# trico_embed01_atmpt01.net
KiCad netlist of a schematic drawn in EAGLE
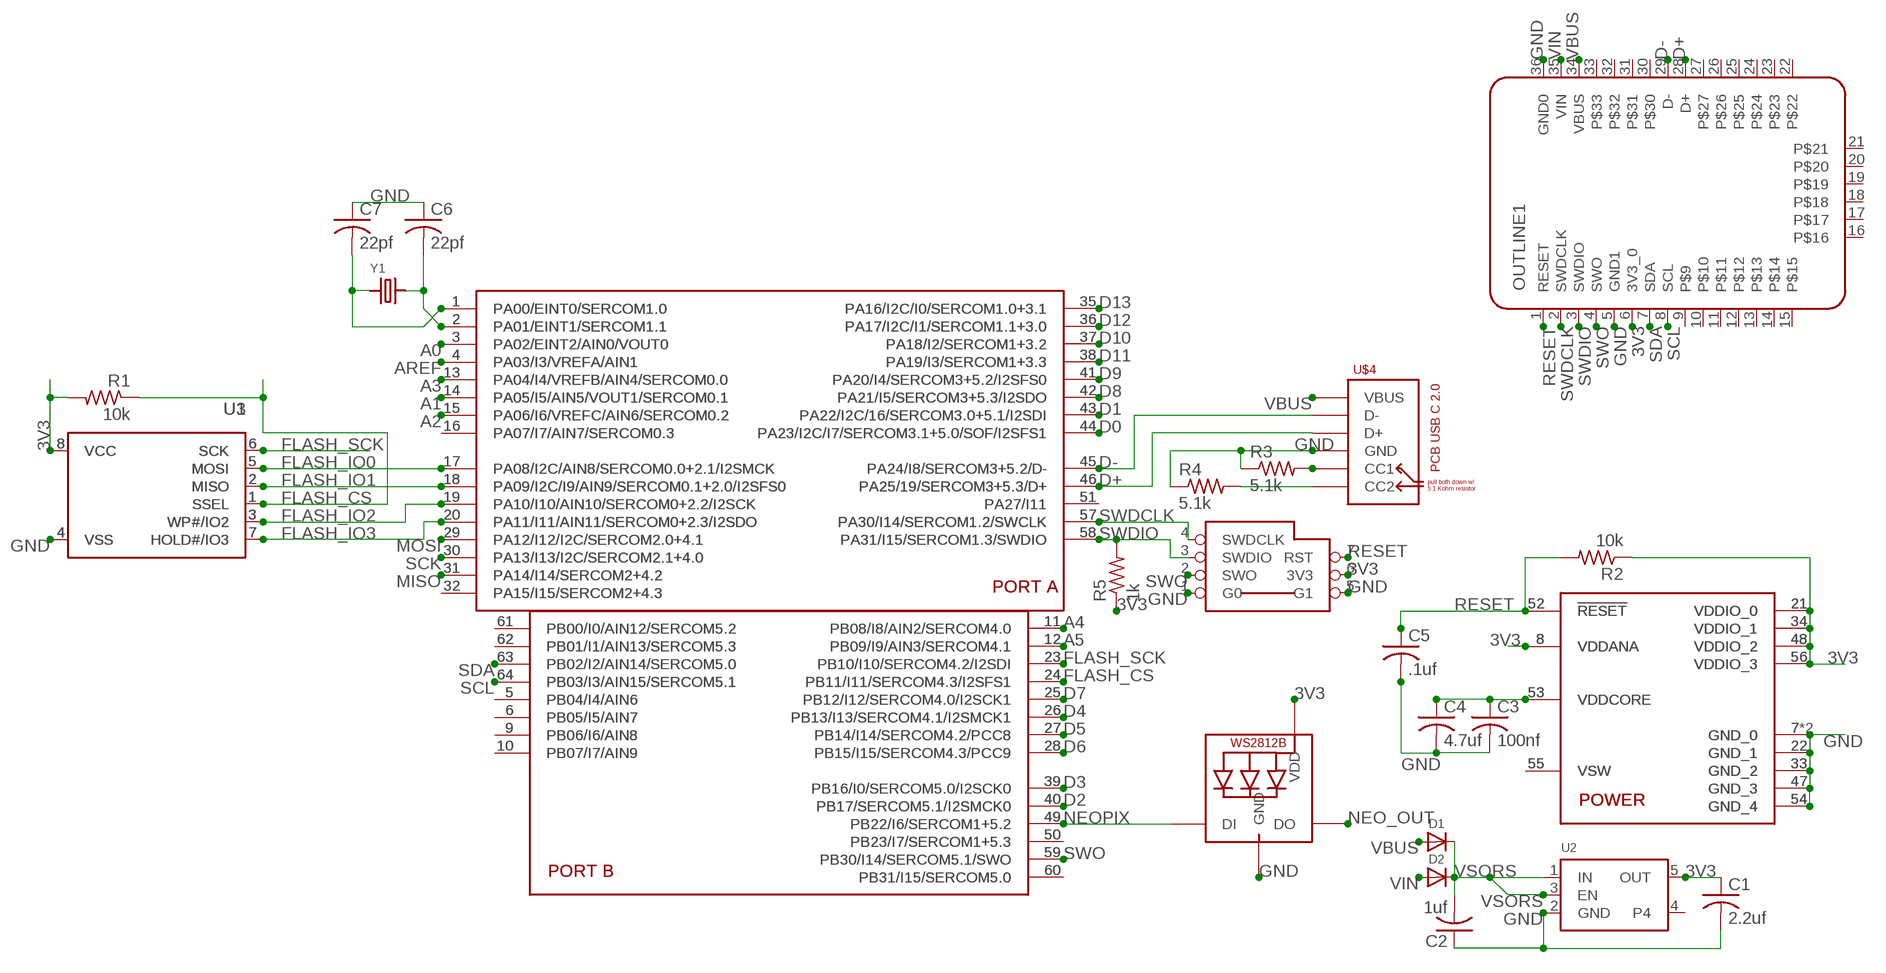
[diagram p0: schematic, sheet 1]

(export (version "E")
  (design (tool "Eeschema 10.0.6"))
  (components
    (comp (ref "C1")
      (value "2.2uf")
      (footprint "eagle-import:TG-C0805MP")
      (libsource (lib "eagle-import") (part "C-TG"))
    )
    (comp (ref "C2")
      (value "1uf")
      (footprint "eagle-import:TG-C0805MP")
      (libsource (lib "eagle-import") (part "C-TG"))
    )
    (comp (ref "C3")
      (value "100nf")
      (footprint "eagle-import:TG-C0805MP")
      (libsource (lib "eagle-import") (part "C-TG"))
    )
    (comp (ref "C4")
      (value "4.7uf")
      (footprint "eagle-import:TG-C0805MP")
      (libsource (lib "eagle-import") (part "C-TG"))
    )
    (comp (ref "C5")
      (value ".1uf")
      (footprint "eagle-import:TG-C0805MP")
      (libsource (lib "eagle-import") (part "C-TG"))
    )
    (comp (ref "C6")
      (value "22pf")
      (footprint "eagle-import:TG-C0805MP")
      (libsource (lib "eagle-import") (part "C-TG"))
    )
    (comp (ref "C7")
      (value "22pf")
      (footprint "eagle-import:TG-C0805MP")
      (libsource (lib "eagle-import") (part "C-TG"))
    )
    (comp (ref "D1")
      (value "DIODESOD-123")
      (footprint "eagle-import:SOD-123")
      (libsource (lib "eagle-import") (part "DIODESOD-123"))
    )
    (comp (ref "D2")
      (value "DIODESOD-123")
      (footprint "eagle-import:SOD-123")
      (libsource (lib "eagle-import") (part "DIODESOD-123"))
    )
    (comp (ref "LED1")
      (value "LED-NEO-WS2812B3535")
      (footprint "eagle-import:LED3535")
      (libsource (lib "eagle-import") (part "LED-NEO-WS2812B3535"))
    )
    (comp (ref "OUTLINE1")
      (value "TRIOC_DEV_36_EMBED_01BREAK")
      (footprint "eagle-import:TRICO_DEV_01_BRK_HYBRID")
      (libsource (lib "eagle-import") (part "TRIOC_DEV_36_EMBED_01BREAK"))
    )
    (comp (ref "R1")
      (value "10k")
      (footprint "eagle-import:TG-R0805")
      (libsource (lib "eagle-import") (part "R_TG"))
    )
    (comp (ref "R2")
      (value "10k")
      (footprint "eagle-import:TG-R0805")
      (libsource (lib "eagle-import") (part "R_TG"))
    )
    (comp (ref "R3")
      (value "5.1k")
      (footprint "eagle-import:TG-R0805")
      (libsource (lib "eagle-import") (part "0TG-Lib v01.4_R_TG"))
    )
    (comp (ref "R4")
      (value "5.1k")
      (footprint "eagle-import:TG-R0805")
      (libsource (lib "eagle-import") (part "0TG-Lib v01.4_R_TG"))
    )
    (comp (ref "R5")
      (value "1k")
      (footprint "eagle-import:TG-R0805")
      (libsource (lib "eagle-import") (part "R_TG"))
    )
    (comp (ref "U$1")
      (value "MCU-ATSAMD51J-ADATQFP")
      (footprint "eagle-import:QFP50P1200X1200X120-64N")
      (libsource (lib "eagle-import") (part "MCU-ATSAMD51J-ADATQFP"))
    )
    (comp (ref "U$2")
      (value "MCU-ATSAMD51J-ADAADA")
      (footprint "eagle-import:MICROBUILDER_PQFN64-1")
      (libsource (lib "eagle-import") (part "0TG-Lib v01.4_MCU-ATSAMD51J-ADAADA"))
    )
    (comp (ref "U$3")
      (value "SWD_POGO")
      (footprint "eagle-import:SWD_POGO")
      (libsource (lib "eagle-import") (part "SWD_POGO"))
    )
    (comp (ref "U$4")
      (value "USB-C-PCB-USB-2.0-TYPE-CDS_2")
      (footprint "eagle-import:USB_TYPE_C_DS_2")
      (libsource (lib "eagle-import") (part "USB-C-PCB-USB-2.0-TYPE-CDS_2"))
    )
    (comp (ref "U1")
      (value "FLASH-SPI-SOIC8")
      (footprint "eagle-import:SOIC8_150MIL")
      (libsource (lib "eagle-import") (part "FLASH-SPI-SOIC8"))
    )
    (comp (ref "U2")
      (value "VREG_STD_MIN_SOT23-5")
      (footprint "eagle-import:SOT23-5")
      (libsource (lib "eagle-import") (part "VREG_STD_MIN_SOT23-5"))
    )
    (comp (ref "U3")
      (value "FLASH-SPI-SOIC8208MIL")
      (footprint "eagle-import:SOIC8_208MIL")
      (libsource (lib "eagle-import") (part "FLASH-SPI-SOIC8208MIL"))
    )
    (comp (ref "Y1")
      (value "XTAL_ADA4.9X1.8")
      (footprint "eagle-import:MICROBUILDER_CRYSTAL_4.9X1.8")
      (libsource (lib "eagle-import") (part "XTAL_ADA4.9X1.8"))
    )
  )
  (nets
    (net (code "1") (name "/3V3") (class "Default")
      (node (ref "C1") (pin "1") (pinfunction "1_1") (pintype "passive"))
      (node (ref "LED1") (pin "2") (pinfunction "VDD_2") (pintype "power_in"))
      (node (ref "OUTLINE1") (pin "6") (pinfunction "3V3_0_6") (pintype "bidirectional"))
      (node (ref "R1") (pin "2") (pinfunction "2_2") (pintype "passive"))
      (node (ref "R2") (pin "1") (pinfunction "1_1") (pintype "passive"))
      (node (ref "R5") (pin "1") (pinfunction "1_1") (pintype "passive"))
      (node (ref "U$1") (pin "21") (pinfunction "VDDIO_0_21") (pintype "bidirectional"))
      (node (ref "U$1") (pin "34") (pinfunction "VDDIO_1_34") (pintype "bidirectional"))
      (node (ref "U$1") (pin "48") (pinfunction "VDDIO_2_48") (pintype "bidirectional"))
      (node (ref "U$1") (pin "56") (pinfunction "VDDIO_3_56") (pintype "bidirectional"))
      (node (ref "U$1") (pin "8") (pinfunction "VDDANA_8") (pintype "bidirectional"))
      (node (ref "U$2") (pin "21") (pinfunction "VDDIO_0_21") (pintype "bidirectional"))
      (node (ref "U$2") (pin "34") (pinfunction "VDDIO_1_34") (pintype "bidirectional"))
      (node (ref "U$2") (pin "48") (pinfunction "VDDIO_2_48") (pintype "bidirectional"))
      (node (ref "U$2") (pin "56") (pinfunction "VDDIO_3_56") (pintype "bidirectional"))
      (node (ref "U$2") (pin "8") (pinfunction "VDDANA_8") (pintype "bidirectional"))
      (node (ref "U$3") (pin "6") (pinfunction "3V3_6") (pintype "bidirectional"))
      (node (ref "U1") (pin "8") (pinfunction "VCC_8") (pintype "bidirectional"))
      (node (ref "U2") (pin "5") (pinfunction "OUT_5") (pintype "power_in"))
      (node (ref "U3") (pin "8") (pinfunction "VCC_8") (pintype "bidirectional"))
    )
    (net (code "2") (name "/A0") (class "Default")
      (node (ref "U$1") (pin "3") (pinfunction "PA02/EINT2/AIN0/VOUT0_3") (pintype "bidirectional"))
      (node (ref "U$2") (pin "3") (pinfunction "PA02/EINT2/AIN0/VOUT0_3") (pintype "bidirectional"))
    )
    (net (code "3") (name "/A1") (class "Default")
      (node (ref "U$1") (pin "14") (pinfunction "PA05/I5/AIN5/VOUT1/SERCOM0.1_14") (pintype "bidirectional"))
      (node (ref "U$2") (pin "14") (pinfunction "PA05/I5/AIN5/VOUT1/SERCOM0.1_14") (pintype "bidirectional"))
    )
    (net (code "4") (name "/A2") (class "Default")
      (node (ref "U$1") (pin "15") (pinfunction "PA06/I6/VREFC/AIN6/SERCOM0.2_15") (pintype "bidirectional"))
      (node (ref "U$2") (pin "15") (pinfunction "PA06/I6/VREFC/AIN6/SERCOM0.2_15") (pintype "bidirectional"))
    )
    (net (code "5") (name "/A3") (class "Default")
      (node (ref "U$1") (pin "13") (pinfunction "PA04/I4/VREFB/AIN4/SERCOM0.0_13") (pintype "bidirectional"))
      (node (ref "U$2") (pin "13") (pinfunction "PA04/I4/VREFB/AIN4/SERCOM0.0_13") (pintype "bidirectional"))
    )
    (net (code "6") (name "/A4") (class "Default")
      (node (ref "U$1") (pin "11") (pinfunction "PB08/I8/AIN2/SERCOM4.0_11") (pintype "bidirectional"))
      (node (ref "U$2") (pin "11") (pinfunction "PB08/I8/AIN2/SERCOM4.0_11") (pintype "bidirectional"))
    )
    (net (code "7") (name "/A5") (class "Default")
      (node (ref "U$1") (pin "12") (pinfunction "PB09/I9/AIN3/SERCOM4.1_12") (pintype "bidirectional"))
      (node (ref "U$2") (pin "12") (pinfunction "PB09/I9/AIN3/SERCOM4.1_12") (pintype "bidirectional"))
    )
    (net (code "8") (name "/AREF") (class "Default")
      (node (ref "U$1") (pin "4") (pinfunction "PA03/I3/VREFA/AIN1_4") (pintype "bidirectional"))
      (node (ref "U$2") (pin "4") (pinfunction "PA03/I3/VREFA/AIN1_4") (pintype "bidirectional"))
    )
    (net (code "9") (name "/D+") (class "Default")
      (node (ref "OUTLINE1") (pin "28") (pinfunction "D+_28") (pintype "bidirectional"))
      (node (ref "U$1") (pin "46") (pinfunction "PA25/19/SERCOM3+5.3/D+_46") (pintype "bidirectional"))
      (node (ref "U$2") (pin "46") (pinfunction "PA25/19/SERCOM3+5.3/D+_46") (pintype "bidirectional"))
      (node (ref "U$4") (pin "A6") (pinfunction "D+_A6") (pintype "bidirectional"))
      (node (ref "U$4") (pin "B6") (pinfunction "D+_B6") (pintype "bidirectional"))
    )
    (net (code "10") (name "/D-") (class "Default")
      (node (ref "OUTLINE1") (pin "29") (pinfunction "D-_29") (pintype "bidirectional"))
      (node (ref "U$1") (pin "45") (pinfunction "PA24/I8/SERCOM3+5.2/D-_45") (pintype "bidirectional"))
      (node (ref "U$2") (pin "45") (pinfunction "PA24/I8/SERCOM3+5.2/D-_45") (pintype "bidirectional"))
      (node (ref "U$4") (pin "A7") (pinfunction "D-_A7") (pintype "bidirectional"))
      (node (ref "U$4") (pin "B7") (pinfunction "D-_B7") (pintype "bidirectional"))
    )
    (net (code "11") (name "/D0") (class "Default")
      (node (ref "U$1") (pin "44") (pinfunction "PA23/I2C/I7/SERCOM3.1+5.0/SOF/I2SFS1_44") (pintype "bidirectional"))
      (node (ref "U$2") (pin "44") (pinfunction "PA23/I2C/I7/SERCOM3.1+5.0/SOF/I2SFS1_44") (pintype "bidirectional"))
    )
    (net (code "12") (name "/D1") (class "Default")
      (node (ref "U$1") (pin "43") (pinfunction "PA22/I2C/16/SERCOM3.0+5.1/I2SDI_43") (pintype "bidirectional"))
      (node (ref "U$2") (pin "43") (pinfunction "PA22/I2C/16/SERCOM3.0+5.1/I2SDI_43") (pintype "bidirectional"))
    )
    (net (code "13") (name "/D2") (class "Default")
      (node (ref "U$1") (pin "40") (pinfunction "PB17/SERCOM5.1/I2SMCK0_40") (pintype "bidirectional"))
      (node (ref "U$2") (pin "40") (pinfunction "PB17/SERCOM5.1/I2SMCK0_40") (pintype "bidirectional"))
    )
    (net (code "14") (name "/D3") (class "Default")
      (node (ref "U$1") (pin "39") (pinfunction "PB16/I0/SERCOM5.0/I2SCK0_39") (pintype "bidirectional"))
      (node (ref "U$2") (pin "39") (pinfunction "PB16/I0/SERCOM5.0/I2SCK0_39") (pintype "bidirectional"))
    )
    (net (code "15") (name "/D4") (class "Default")
      (node (ref "U$1") (pin "26") (pinfunction "PB13/I13/SERCOM4.1/I2SMCK1_26") (pintype "bidirectional"))
      (node (ref "U$2") (pin "26") (pinfunction "PB13/I13/SERCOM4.1/I2SMCK1_26") (pintype "bidirectional"))
    )
    (net (code "16") (name "/D5") (class "Default")
      (node (ref "U$1") (pin "27") (pinfunction "PB14/I14/SERCOM4.2/PCC8_27") (pintype "bidirectional"))
      (node (ref "U$2") (pin "27") (pinfunction "PB14/I14/SERCOM4.2/PCC8_27") (pintype "bidirectional"))
    )
    (net (code "17") (name "/D6") (class "Default")
      (node (ref "U$1") (pin "28") (pinfunction "PB15/I15/SERCOM4.3/PCC9_28") (pintype "bidirectional"))
      (node (ref "U$2") (pin "28") (pinfunction "PB15/I15/SERCOM4.3/PCC9_28") (pintype "bidirectional"))
    )
    (net (code "18") (name "/D7") (class "Default")
      (node (ref "U$1") (pin "25") (pinfunction "PB12/I12/SERCOM4.0/I2SCK1_25") (pintype "bidirectional"))
      (node (ref "U$2") (pin "25") (pinfunction "PB12/I12/SERCOM4.0/I2SCK1_25") (pintype "bidirectional"))
    )
    (net (code "19") (name "/D8") (class "Default")
      (node (ref "U$1") (pin "42") (pinfunction "PA21/I5/SERCOM3+5.3/I2SDO_42") (pintype "bidirectional"))
      (node (ref "U$2") (pin "42") (pinfunction "PA21/I5/SERCOM3+5.3/I2SDO_42") (pintype "bidirectional"))
    )
    (net (code "20") (name "/D9") (class "Default")
      (node (ref "U$1") (pin "41") (pinfunction "PA20/I4/SERCOM3+5.2/I2SFS0_41") (pintype "bidirectional"))
      (node (ref "U$2") (pin "41") (pinfunction "PA20/I4/SERCOM3+5.2/I2SFS0_41") (pintype "bidirectional"))
    )
    (net (code "21") (name "/D10") (class "Default")
      (node (ref "U$1") (pin "37") (pinfunction "PA18/I2/SERCOM1+3.2_37") (pintype "bidirectional"))
      (node (ref "U$2") (pin "37") (pinfunction "PA18/I2/SERCOM1+3.2_37") (pintype "bidirectional"))
    )
    (net (code "22") (name "/D11") (class "Default")
      (node (ref "U$1") (pin "38") (pinfunction "PA19/I3/SERCOM1+3.3_38") (pintype "bidirectional"))
      (node (ref "U$2") (pin "38") (pinfunction "PA19/I3/SERCOM1+3.3_38") (pintype "bidirectional"))
    )
    (net (code "23") (name "/D12") (class "Default")
      (node (ref "U$1") (pin "36") (pinfunction "PA17/I2C/I1/SERCOM1.1+3.0_36") (pintype "bidirectional"))
      (node (ref "U$2") (pin "36") (pinfunction "PA17/I2C/I1/SERCOM1.1+3.0_36") (pintype "bidirectional"))
    )
    (net (code "24") (name "/D13") (class "Default")
      (node (ref "U$1") (pin "35") (pinfunction "PA16/I2C/I0/SERCOM1.0+3.1_35") (pintype "bidirectional"))
      (node (ref "U$2") (pin "35") (pinfunction "PA16/I2C/I0/SERCOM1.0+3.1_35") (pintype "bidirectional"))
    )
    (net (code "25") (name "/FLASH_CS") (class "Default")
      (node (ref "R1") (pin "1") (pinfunction "1_1") (pintype "passive"))
      (node (ref "U$1") (pin "24") (pinfunction "PB11/I11/SERCOM4.3/I2SFS1_24") (pintype "bidirectional"))
      (node (ref "U$2") (pin "24") (pinfunction "PB11/I11/SERCOM4.3/I2SFS1_24") (pintype "bidirectional"))
      (node (ref "U1") (pin "1") (pinfunction "SSEL_1") (pintype "bidirectional"))
      (node (ref "U3") (pin "1") (pinfunction "SSEL_1") (pintype "bidirectional"))
    )
    (net (code "26") (name "/FLASH_IO0") (class "Default")
      (node (ref "U$1") (pin "17") (pinfunction "PA08/I2C/AIN8/SERCOM0.0+2.1/I2SMCK_17") (pintype "bidirectional"))
      (node (ref "U$2") (pin "17") (pinfunction "PA08/I2C/AIN8/SERCOM0.0+2.1/I2SMCK_17") (pintype "bidirectional"))
      (node (ref "U1") (pin "5") (pinfunction "MOSI_5") (pintype "bidirectional"))
      (node (ref "U3") (pin "5") (pinfunction "MOSI_5") (pintype "bidirectional"))
    )
    (net (code "27") (name "/FLASH_IO1") (class "Default")
      (node (ref "U$1") (pin "18") (pinfunction "PA09/I2C/I9/AIN9/SERCOM0.1+2.0/I2SFS0_18") (pintype "bidirectional"))
      (node (ref "U$2") (pin "18") (pinfunction "PA09/I2C/I9/AIN9/SERCOM0.1+2.0/I2SFS0_18") (pintype "bidirectional"))
      (node (ref "U1") (pin "2") (pinfunction "MISO_2") (pintype "bidirectional"))
      (node (ref "U3") (pin "2") (pinfunction "MISO_2") (pintype "bidirectional"))
    )
    (net (code "28") (name "/FLASH_IO2") (class "Default")
      (node (ref "U$1") (pin "19") (pinfunction "PA10/I10/AIN10/SERCOM0+2.2/I2SCK_19") (pintype "bidirectional"))
      (node (ref "U$2") (pin "19") (pinfunction "PA10/I10/AIN10/SERCOM0+2.2/I2SCK_19") (pintype "bidirectional"))
      (node (ref "U1") (pin "3") (pinfunction "WP#/IO2_3") (pintype "bidirectional"))
      (node (ref "U3") (pin "3") (pinfunction "WP#/IO2_3") (pintype "bidirectional"))
    )
    (net (code "29") (name "/FLASH_IO3") (class "Default")
      (node (ref "U$1") (pin "20") (pinfunction "PA11/I11/AIN11/SERCOM0+2.3/I2SDO_20") (pintype "bidirectional"))
      (node (ref "U$2") (pin "20") (pinfunction "PA11/I11/AIN11/SERCOM0+2.3/I2SDO_20") (pintype "bidirectional"))
      (node (ref "U1") (pin "7") (pinfunction "HOLD#/IO3_7") (pintype "bidirectional"))
      (node (ref "U3") (pin "7") (pinfunction "HOLD#/IO3_7") (pintype "bidirectional"))
    )
    (net (code "30") (name "/FLASH_SCK") (class "Default")
      (node (ref "U$1") (pin "23") (pinfunction "PB10/I10/SERCOM4.2/I2SDI_23") (pintype "bidirectional"))
      (node (ref "U$2") (pin "23") (pinfunction "PB10/I10/SERCOM4.2/I2SDI_23") (pintype "bidirectional"))
      (node (ref "U1") (pin "6") (pinfunction "SCK_6") (pintype "bidirectional"))
      (node (ref "U3") (pin "6") (pinfunction "SCK_6") (pintype "bidirectional"))
    )
    (net (code "31") (name "/GND") (class "Default")
      (node (ref "C1") (pin "2") (pinfunction "2_2") (pintype "passive"))
      (node (ref "C2") (pin "1") (pinfunction "1_1") (pintype "passive"))
      (node (ref "C3") (pin "2") (pinfunction "2_2") (pintype "passive"))
      (node (ref "C4") (pin "2") (pinfunction "2_2") (pintype "passive"))
      (node (ref "C5") (pin "2") (pinfunction "2_2") (pintype "passive"))
      (node (ref "C6") (pin "1") (pinfunction "1_1") (pintype "passive"))
      (node (ref "C7") (pin "1") (pinfunction "1_1") (pintype "passive"))
      (node (ref "LED1") (pin "4") (pinfunction "GND_4") (pintype "power_in"))
      (node (ref "OUTLINE1") (pin "36") (pinfunction "GND0_36") (pintype "bidirectional"))
      (node (ref "OUTLINE1") (pin "5") (pinfunction "GND1_5") (pintype "bidirectional"))
      (node (ref "R3") (pin "1") (pinfunction "1_1") (pintype "passive"))
      (node (ref "R4") (pin "1") (pinfunction "1_1") (pintype "passive"))
      (node (ref "U$1") (pin "22") (pinfunction "GND_1_22") (pintype "bidirectional"))
      (node (ref "U$1") (pin "33") (pinfunction "GND_2_33") (pintype "bidirectional"))
      (node (ref "U$1") (pin "47") (pinfunction "GND_3_47") (pintype "bidirectional"))
      (node (ref "U$1") (pin "54") (pinfunction "GND_4_54") (pintype "bidirectional"))
      (node (ref "U$1") (pin "7") (pinfunction "GND_0_7") (pintype "bidirectional"))
      (node (ref "U$2") (pin "22") (pinfunction "GND_1_22") (pintype "bidirectional"))
      (node (ref "U$2") (pin "33") (pinfunction "GND_2_33") (pintype "bidirectional"))
      (node (ref "U$2") (pin "47") (pinfunction "GND_3_47") (pintype "bidirectional"))
      (node (ref "U$2") (pin "54") (pinfunction "GND_4_54") (pintype "bidirectional"))
      (node (ref "U$2") (pin "7") (pinfunction "GND_0_7") (pintype "bidirectional"))
      (node (ref "U$2") (pin "EXP") (pinfunction "GND_0_EXP") (pintype "bidirectional"))
      (node (ref "U$3") (pin "1") (pinfunction "G0_1") (pintype "bidirectional"))
      (node (ref "U$3") (pin "5") (pinfunction "G1_5") (pintype "bidirectional"))
      (node (ref "U$4") (pin "A1") (pinfunction "GND_A1") (pintype "bidirectional"))
      (node (ref "U$4") (pin "A12") (pinfunction "GND_A12") (pintype "bidirectional"))
      (node (ref "U$4") (pin "B1") (pinfunction "GND_B1") (pintype "bidirectional"))
      (node (ref "U$4") (pin "B12") (pinfunction "GND_B12") (pintype "bidirectional"))
      (node (ref "U1") (pin "4") (pinfunction "VSS_4") (pintype "bidirectional"))
      (node (ref "U2") (pin "2") (pinfunction "GND_2") (pintype "power_in"))
      (node (ref "U3") (pin "4") (pinfunction "VSS_4") (pintype "bidirectional"))
    )
    (net (code "32") (name "/MISO") (class "Default")
      (node (ref "U$1") (pin "31") (pinfunction "PA14/I14/SERCOM2+4.2_31") (pintype "bidirectional"))
      (node (ref "U$2") (pin "31") (pinfunction "PA14/I14/SERCOM2+4.2_31") (pintype "bidirectional"))
    )
    (net (code "33") (name "/MOSI") (class "Default")
      (node (ref "U$1") (pin "29") (pinfunction "PA12/I12/I2C/SERCOM2.0+4.1_29") (pintype "bidirectional"))
      (node (ref "U$2") (pin "29") (pinfunction "PA12/I12/I2C/SERCOM2.0+4.1_29") (pintype "bidirectional"))
    )
    (net (code "34") (name "/NEOPIX") (class "Default")
      (node (ref "LED1") (pin "1") (pinfunction "DI_1") (pintype "input"))
      (node (ref "U$1") (pin "49") (pinfunction "PB22/I6/SERCOM1+5.2_49") (pintype "bidirectional"))
      (node (ref "U$2") (pin "49") (pinfunction "PB22/I6/SERCOM1+5.2_49") (pintype "bidirectional"))
    )
    (net (code "35") (name "/NEO_OUT") (class "Default")
      (node (ref "LED1") (pin "3") (pinfunction "DO_3") (pintype "output"))
    )
    (net (code "36") (name "/RESET") (class "Default")
      (node (ref "C5") (pin "1") (pinfunction "1_1") (pintype "passive"))
      (node (ref "OUTLINE1") (pin "1") (pinfunction "RESET_1") (pintype "bidirectional"))
      (node (ref "R2") (pin "2") (pinfunction "2_2") (pintype "passive"))
      (node (ref "U$1") (pin "52") (pinfunction "~{RESET}_52") (pintype "bidirectional"))
      (node (ref "U$2") (pin "52") (pinfunction "~{RESET}_52") (pintype "bidirectional"))
      (node (ref "U$3") (pin "7") (pinfunction "RST_7") (pintype "bidirectional"))
    )
    (net (code "37") (name "/SCK") (class "Default")
      (node (ref "U$1") (pin "30") (pinfunction "PA13/I13/I2C/SERCOM2.1+4.0_30") (pintype "bidirectional"))
      (node (ref "U$2") (pin "30") (pinfunction "PA13/I13/I2C/SERCOM2.1+4.0_30") (pintype "bidirectional"))
    )
    (net (code "38") (name "/SCL") (class "Default")
      (node (ref "OUTLINE1") (pin "8") (pinfunction "SCL_8") (pintype "bidirectional"))
      (node (ref "U$1") (pin "64") (pinfunction "PB03/I3/AIN15/SERCOM5.1_64") (pintype "bidirectional"))
      (node (ref "U$2") (pin "64") (pinfunction "PB03/I3/AIN15/SERCOM5.1_64") (pintype "bidirectional"))
    )
    (net (code "39") (name "/SDA") (class "Default")
      (node (ref "OUTLINE1") (pin "7") (pinfunction "SDA_7") (pintype "bidirectional"))
      (node (ref "U$1") (pin "63") (pinfunction "PB02/I2/AIN14/SERCOM5.0_63") (pintype "bidirectional"))
      (node (ref "U$2") (pin "63") (pinfunction "PB02/I2/AIN14/SERCOM5.0_63") (pintype "bidirectional"))
    )
    (net (code "40") (name "/SWDCLK") (class "Default")
      (node (ref "OUTLINE1") (pin "2") (pinfunction "SWDCLK_2") (pintype "bidirectional"))
      (node (ref "U$1") (pin "57") (pinfunction "PA30/I14/SERCOM1.2/SWCLK_57") (pintype "bidirectional"))
      (node (ref "U$2") (pin "57") (pinfunction "PA30/I14/SERCOM1.2/SWCLK_57") (pintype "bidirectional"))
      (node (ref "U$3") (pin "4") (pinfunction "SWDCLK_4") (pintype "bidirectional"))
    )
    (net (code "41") (name "/SWDIO") (class "Default")
      (node (ref "OUTLINE1") (pin "3") (pinfunction "SWDIO_3") (pintype "bidirectional"))
      (node (ref "R5") (pin "2") (pinfunction "2_2") (pintype "passive"))
      (node (ref "U$1") (pin "58") (pinfunction "PA31/I15/SERCOM1.3/SWDIO_58") (pintype "bidirectional"))
      (node (ref "U$2") (pin "58") (pinfunction "PA31/I15/SERCOM1.3/SWDIO_58") (pintype "bidirectional"))
      (node (ref "U$3") (pin "3") (pinfunction "SWDIO_3") (pintype "bidirectional"))
    )
    (net (code "42") (name "/SWO") (class "Default")
      (node (ref "OUTLINE1") (pin "4") (pinfunction "SWO_4") (pintype "bidirectional"))
      (node (ref "U$1") (pin "59") (pinfunction "PB30/I14/SERCOM5.1/SWO_59") (pintype "bidirectional"))
      (node (ref "U$2") (pin "59") (pinfunction "PB30/I14/SERCOM5.1/SWO_59") (pintype "bidirectional"))
      (node (ref "U$3") (pin "2") (pinfunction "SWO_2") (pintype "bidirectional"))
    )
    (net (code "43") (name "/VBUS") (class "Default")
      (node (ref "D1") (pin "A") (pinfunction "A_A") (pintype "passive"))
      (node (ref "OUTLINE1") (pin "34") (pinfunction "VBUS_34") (pintype "bidirectional"))
      (node (ref "U$4") (pin "A4") (pinfunction "VBUS_A4") (pintype "bidirectional"))
      (node (ref "U$4") (pin "A9") (pinfunction "VBUS_A9") (pintype "bidirectional"))
      (node (ref "U$4") (pin "B4") (pinfunction "VBUS_B4") (pintype "bidirectional"))
      (node (ref "U$4") (pin "B9") (pinfunction "VBUS_B9") (pintype "bidirectional"))
    )
    (net (code "44") (name "/VIN") (class "Default")
      (node (ref "D2") (pin "A") (pinfunction "A_A") (pintype "passive"))
      (node (ref "OUTLINE1") (pin "35") (pinfunction "VIN_35") (pintype "bidirectional"))
    )
    (net (code "45") (name "/VSORS") (class "Default")
      (node (ref "C2") (pin "2") (pinfunction "2_2") (pintype "passive"))
      (node (ref "D1") (pin "C") (pinfunction "C_C") (pintype "passive"))
      (node (ref "D2") (pin "C") (pinfunction "C_C") (pintype "passive"))
      (node (ref "U2") (pin "1") (pinfunction "IN_1") (pintype "power_in"))
      (node (ref "U2") (pin "3") (pinfunction "EN_3") (pintype "input"))
    )
    (net (code "46") (name "Net-(U$1A-PA00{slash}EINT0{slash}SERCOM1.0)") (class "Default")
      (node (ref "C7") (pin "2") (pinfunction "2_2") (pintype "passive"))
      (node (ref "U$1") (pin "1") (pinfunction "PA00/EINT0/SERCOM1.0_1") (pintype "bidirectional"))
      (node (ref "U$2") (pin "1") (pinfunction "PA00/EINT0/SERCOM1.0_1") (pintype "bidirectional"))
      (node (ref "Y1") (pin "1") (pinfunction "1_1") (pintype "passive"))
    )
    (net (code "47") (name "Net-(U$1A-PA01{slash}EINT1{slash}SERCOM1.1)") (class "Default")
      (node (ref "C6") (pin "2") (pinfunction "2_2") (pintype "passive"))
      (node (ref "U$1") (pin "2") (pinfunction "PA01/EINT1/SERCOM1.1_2") (pintype "bidirectional"))
      (node (ref "U$2") (pin "2") (pinfunction "PA01/EINT1/SERCOM1.1_2") (pintype "bidirectional"))
      (node (ref "Y1") (pin "2") (pinfunction "2_2") (pintype "passive"))
    )
    (net (code "48") (name "Net-(U$1A-PA07{slash}I7{slash}AIN7{slash}SERCOM0.3)") (class "Default")
      (node (ref "U$1") (pin "16") (pinfunction "PA07/I7/AIN7/SERCOM0.3_16") (pintype "bidirectional"))
      (node (ref "U$2") (pin "16") (pinfunction "PA07/I7/AIN7/SERCOM0.3_16") (pintype "bidirectional"))
    )
    (net (code "49") (name "Net-(U$1A-PA15{slash}I15{slash}SERCOM2+4.3)") (class "Default")
      (node (ref "U$1") (pin "32") (pinfunction "PA15/I15/SERCOM2+4.3_32") (pintype "bidirectional"))
      (node (ref "U$2") (pin "32") (pinfunction "PA15/I15/SERCOM2+4.3_32") (pintype "bidirectional"))
    )
    (net (code "50") (name "Net-(U$1A-PA27{slash}I11)") (class "Default")
      (node (ref "U$1") (pin "51") (pinfunction "PA27/I11_51") (pintype "bidirectional"))
      (node (ref "U$2") (pin "51") (pinfunction "PA27/I11_51") (pintype "bidirectional"))
    )
    (net (code "51") (name "Net-(U$1B-PB00{slash}I0{slash}AIN12{slash}SERCOM5.2)") (class "Default")
      (node (ref "U$1") (pin "61") (pinfunction "PB00/I0/AIN12/SERCOM5.2_61") (pintype "bidirectional"))
      (node (ref "U$2") (pin "61") (pinfunction "PB00/I0/AIN12/SERCOM5.2_61") (pintype "bidirectional"))
    )
    (net (code "52") (name "Net-(U$1B-PB01{slash}I1{slash}AIN13{slash}SERCOM5.3)") (class "Default")
      (node (ref "U$1") (pin "62") (pinfunction "PB01/I1/AIN13/SERCOM5.3_62") (pintype "bidirectional"))
      (node (ref "U$2") (pin "62") (pinfunction "PB01/I1/AIN13/SERCOM5.3_62") (pintype "bidirectional"))
    )
    (net (code "53") (name "Net-(U$1B-PB04{slash}I4{slash}AIN6)") (class "Default")
      (node (ref "U$1") (pin "5") (pinfunction "PB04/I4/AIN6_5") (pintype "bidirectional"))
      (node (ref "U$2") (pin "5") (pinfunction "PB04/I4/AIN6_5") (pintype "bidirectional"))
    )
    (net (code "54") (name "Net-(U$1B-PB05{slash}I5{slash}AIN7)") (class "Default")
      (node (ref "U$1") (pin "6") (pinfunction "PB05/I5/AIN7_6") (pintype "bidirectional"))
      (node (ref "U$2") (pin "6") (pinfunction "PB05/I5/AIN7_6") (pintype "bidirectional"))
    )
    (net (code "55") (name "Net-(U$1B-PB06{slash}I6{slash}AIN8)") (class "Default")
      (node (ref "U$1") (pin "9") (pinfunction "PB06/I6/AIN8_9") (pintype "bidirectional"))
      (node (ref "U$2") (pin "9") (pinfunction "PB06/I6/AIN8_9") (pintype "bidirectional"))
    )
    (net (code "56") (name "Net-(U$1B-PB07{slash}I7{slash}AIN9)") (class "Default")
      (node (ref "U$1") (pin "10") (pinfunction "PB07/I7/AIN9_10") (pintype "bidirectional"))
      (node (ref "U$2") (pin "10") (pinfunction "PB07/I7/AIN9_10") (pintype "bidirectional"))
    )
    (net (code "57") (name "Net-(U$1B-PB23{slash}I7{slash}SERCOM1+5.3)") (class "Default")
      (node (ref "U$1") (pin "50") (pinfunction "PB23/I7/SERCOM1+5.3_50") (pintype "bidirectional"))
      (node (ref "U$2") (pin "50") (pinfunction "PB23/I7/SERCOM1+5.3_50") (pintype "bidirectional"))
    )
    (net (code "58") (name "Net-(U$1B-PB31{slash}I15{slash}SERCOM5.0)") (class "Default")
      (node (ref "U$1") (pin "60") (pinfunction "PB31/I15/SERCOM5.0_60") (pintype "bidirectional"))
      (node (ref "U$2") (pin "60") (pinfunction "PB31/I15/SERCOM5.0_60") (pintype "bidirectional"))
    )
    (net (code "59") (name "Net-(U$1C-VDDCORE)") (class "Default")
      (node (ref "C3") (pin "1") (pinfunction "1_1") (pintype "passive"))
      (node (ref "C4") (pin "1") (pinfunction "1_1") (pintype "passive"))
      (node (ref "U$1") (pin "53") (pinfunction "VDDCORE_53") (pintype "bidirectional"))
      (node (ref "U$2") (pin "53") (pinfunction "VDDCORE_53") (pintype "bidirectional"))
    )
    (net (code "60") (name "Net-(U$1C-VSW)") (class "Default")
      (node (ref "U$1") (pin "55") (pinfunction "VSW_55") (pintype "bidirectional"))
      (node (ref "U$2") (pin "55") (pinfunction "VSW_55") (pintype "bidirectional"))
    )
    (net (code "61") (name "Net-(U$4-CC1)") (class "Default")
      (node (ref "R3") (pin "2") (pinfunction "2_2") (pintype "passive"))
      (node (ref "U$4") (pin "A5") (pinfunction "CC1_A5") (pintype "bidirectional"))
    )
    (net (code "62") (name "Net-(U$4-CC2)") (class "Default")
      (node (ref "R4") (pin "2") (pinfunction "2_2") (pintype "passive"))
      (node (ref "U$4") (pin "B5") (pinfunction "CC2_B5") (pintype "bidirectional"))
    )
    (net (code "63") (name "unconnected-(OUTLINE1-P$9-Pad9)") (class "Default")
      (node (ref "OUTLINE1") (pin "9") (pinfunction "P$9_9") (pintype "bidirectional"))
    )
    (net (code "64") (name "unconnected-(OUTLINE1-P$10-Pad10)") (class "Default")
      (node (ref "OUTLINE1") (pin "10") (pinfunction "P$10_10") (pintype "bidirectional"))
    )
    (net (code "65") (name "unconnected-(OUTLINE1-P$11-Pad11)") (class "Default")
      (node (ref "OUTLINE1") (pin "11") (pinfunction "P$11_11") (pintype "bidirectional"))
    )
    (net (code "66") (name "unconnected-(OUTLINE1-P$12-Pad12)") (class "Default")
      (node (ref "OUTLINE1") (pin "12") (pinfunction "P$12_12") (pintype "bidirectional"))
    )
    (net (code "67") (name "unconnected-(OUTLINE1-P$13-Pad13)") (class "Default")
      (node (ref "OUTLINE1") (pin "13") (pinfunction "P$13_13") (pintype "bidirectional"))
    )
    (net (code "68") (name "unconnected-(OUTLINE1-P$14-Pad14)") (class "Default")
      (node (ref "OUTLINE1") (pin "14") (pinfunction "P$14_14") (pintype "bidirectional"))
    )
    (net (code "69") (name "unconnected-(OUTLINE1-P$15-Pad15)") (class "Default")
      (node (ref "OUTLINE1") (pin "15") (pinfunction "P$15_15") (pintype "bidirectional"))
    )
    (net (code "70") (name "unconnected-(OUTLINE1-P$16-Pad16)") (class "Default")
      (node (ref "OUTLINE1") (pin "16") (pinfunction "P$16_16") (pintype "bidirectional"))
    )
    (net (code "71") (name "unconnected-(OUTLINE1-P$17-Pad17)") (class "Default")
      (node (ref "OUTLINE1") (pin "17") (pinfunction "P$17_17") (pintype "bidirectional"))
    )
    (net (code "72") (name "unconnected-(OUTLINE1-P$18-Pad18)") (class "Default")
      (node (ref "OUTLINE1") (pin "18") (pinfunction "P$18_18") (pintype "bidirectional"))
    )
    (net (code "73") (name "unconnected-(OUTLINE1-P$19-Pad19)") (class "Default")
      (node (ref "OUTLINE1") (pin "19") (pinfunction "P$19_19") (pintype "bidirectional"))
    )
    (net (code "74") (name "unconnected-(OUTLINE1-P$20-Pad20)") (class "Default")
      (node (ref "OUTLINE1") (pin "20") (pinfunction "P$20_20") (pintype "bidirectional"))
    )
    (net (code "75") (name "unconnected-(OUTLINE1-P$21-Pad21)") (class "Default")
      (node (ref "OUTLINE1") (pin "21") (pinfunction "P$21_21") (pintype "bidirectional"))
    )
    (net (code "76") (name "unconnected-(OUTLINE1-P$22-Pad22)") (class "Default")
      (node (ref "OUTLINE1") (pin "22") (pinfunction "P$22_22") (pintype "bidirectional"))
    )
    (net (code "77") (name "unconnected-(OUTLINE1-P$23-Pad23)") (class "Default")
      (node (ref "OUTLINE1") (pin "23") (pinfunction "P$23_23") (pintype "bidirectional"))
    )
    (net (code "78") (name "unconnected-(OUTLINE1-P$24-Pad24)") (class "Default")
      (node (ref "OUTLINE1") (pin "24") (pinfunction "P$24_24") (pintype "bidirectional"))
    )
    (net (code "79") (name "unconnected-(OUTLINE1-P$25-Pad25)") (class "Default")
      (node (ref "OUTLINE1") (pin "25") (pinfunction "P$25_25") (pintype "bidirectional"))
    )
    (net (code "80") (name "unconnected-(OUTLINE1-P$26-Pad26)") (class "Default")
      (node (ref "OUTLINE1") (pin "26") (pinfunction "P$26_26") (pintype "bidirectional"))
    )
    (net (code "81") (name "unconnected-(OUTLINE1-P$27-Pad27)") (class "Default")
      (node (ref "OUTLINE1") (pin "27") (pinfunction "P$27_27") (pintype "bidirectional"))
    )
    (net (code "82") (name "unconnected-(OUTLINE1-P$30-Pad30)") (class "Default")
      (node (ref "OUTLINE1") (pin "30") (pinfunction "P$30_30") (pintype "bidirectional"))
    )
    (net (code "83") (name "unconnected-(OUTLINE1-P$31-Pad31)") (class "Default")
      (node (ref "OUTLINE1") (pin "31") (pinfunction "P$31_31") (pintype "bidirectional"))
    )
    (net (code "84") (name "unconnected-(OUTLINE1-P$32-Pad32)") (class "Default")
      (node (ref "OUTLINE1") (pin "32") (pinfunction "P$32_32") (pintype "bidirectional"))
    )
    (net (code "85") (name "unconnected-(OUTLINE1-P$33-Pad33)") (class "Default")
      (node (ref "OUTLINE1") (pin "33") (pinfunction "P$33_33") (pintype "bidirectional"))
    )
    (net (code "86") (name "unconnected-(U2-P4-Pad4)") (class "Default")
      (node (ref "U2") (pin "4") (pinfunction "P4_4") (pintype "bidirectional"))
    )
  )
)
